# SparkFun_Qwiic_FS3000_1X1.net
KiCad netlist of a schematic drawn in EAGLE
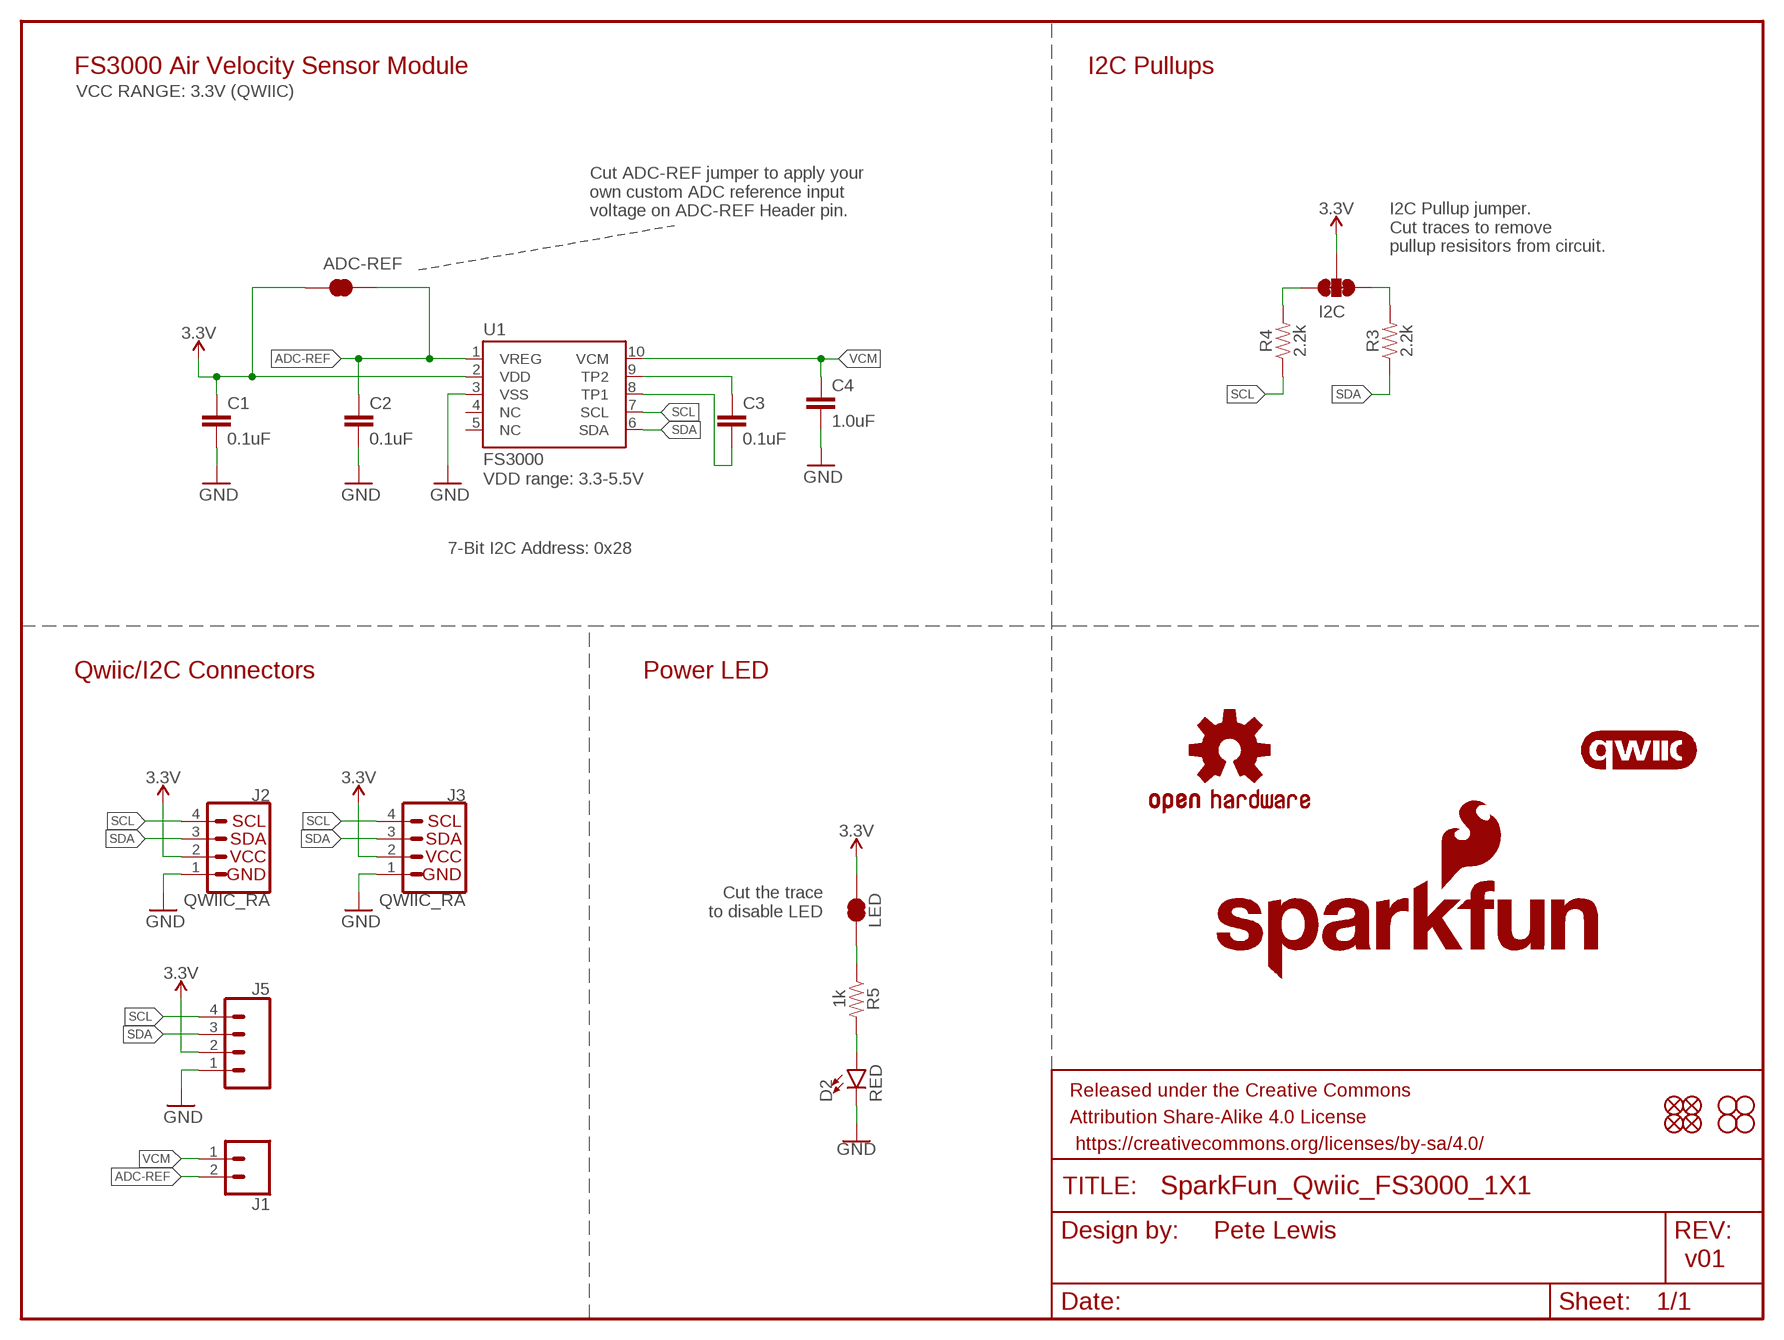
[diagram p0: schematic, sheet 1]

(export (version "E")
  (design (tool "Eeschema 10.0.6"))
  (components
    (comp (ref "ADC-REF")
      (value "JUMPER-SMT_2_NC_TRACE_SILK")
      (footprint "eagle-import:SMT-JUMPER_2_NC_TRACE_SILK")
      (libsource (lib "eagle-import") (part "JUMPER-SMT_2_NC_TRACE_SILK"))
    )
    (comp (ref "C1")
      (value "0.1uF")
      (footprint "eagle-import:0402-TIGHT")
      (libsource (lib "eagle-import") (part "0.1UF-0402T-16V-10%"))
    )
    (comp (ref "C2")
      (value "0.1uF")
      (footprint "eagle-import:0402-TIGHT")
      (libsource (lib "eagle-import") (part "0.1UF-0402T-16V-10%"))
    )
    (comp (ref "C3")
      (value "0.1uF")
      (footprint "eagle-import:0402-TIGHT")
      (libsource (lib "eagle-import") (part "0.1UF-0402T-16V-10%"))
    )
    (comp (ref "C4")
      (value "1.0uF")
      (footprint "eagle-import:0402-TIGHT")
      (libsource (lib "eagle-import") (part "1.0UF-0402T-16V-10%"))
    )
    (comp (ref "D2")
      (value "RED")
      (footprint "eagle-import:LED-0603")
      (libsource (lib "eagle-import") (part "LED-RED0603"))
    )
    (comp (ref "FRAME1")
      (value "FRAME-LETTER")
      (footprint "eagle-import:CREATIVE_COMMONS")
      (libsource (lib "eagle-import") (part "FRAME-LETTER"))
    )
    (comp (ref "I2C")
      (value "JUMPER-SMT_3_2-NC_TRACE_SILK")
      (footprint "eagle-import:SMT-JUMPER_3_2-NC_TRACE_SILK")
      (libsource (lib "eagle-import") (part "JUMPER-SMT_3_2-NC_TRACE_SILK"))
    )
    (comp (ref "J1")
      (value "CONN_021X02_NO_SILK")
      (footprint "eagle-import:1X02_NO_SILK")
      (libsource (lib "eagle-import") (part "CONN_021X02_NO_SILK"))
    )
    (comp (ref "J2")
      (value "QWIIC_RA")
      (footprint "eagle-import:JST04_1MM_RA")
      (libsource (lib "eagle-import") (part "QWIIC_CONNECTORJS-1MM"))
    )
    (comp (ref "J3")
      (value "QWIIC_RA")
      (footprint "eagle-import:JST04_1MM_RA")
      (libsource (lib "eagle-import") (part "QWIIC_CONNECTORJS-1MM"))
    )
    (comp (ref "J5")
      (value "CONN_041X04_NO_SILK")
      (footprint "eagle-import:1X04_NO_SILK")
      (libsource (lib "eagle-import") (part "CONN_041X04_NO_SILK"))
    )
    (comp (ref "JP1")
      (value "LED")
      (footprint "eagle-import:SMT-JUMPER_2_NC_TRACE_SILK")
      (libsource (lib "eagle-import") (part "JUMPER-SMT_2_NC_TRACE_SILK"))
    )
    (comp (ref "JP2")
      (value "FIDUCIALUFIDUCIAL")
      (footprint "eagle-import:FIDUCIAL-MICRO")
      (libsource (lib "eagle-import") (part "FIDUCIALUFIDUCIAL"))
    )
    (comp (ref "JP3")
      (value "STAND-OFF")
      (footprint "eagle-import:STAND-OFF")
      (libsource (lib "eagle-import") (part "STAND-OFF"))
    )
    (comp (ref "JP4")
      (value "STAND-OFF")
      (footprint "eagle-import:STAND-OFF")
      (libsource (lib "eagle-import") (part "STAND-OFF"))
    )
    (comp (ref "JP5")
      (value "FIDUCIALUFIDUCIAL")
      (footprint "eagle-import:FIDUCIAL-MICRO")
      (libsource (lib "eagle-import") (part "FIDUCIALUFIDUCIAL"))
    )
    (comp (ref "JP6")
      (value "FIDUCIALUFIDUCIAL")
      (footprint "eagle-import:FIDUCIAL-MICRO")
      (libsource (lib "eagle-import") (part "FIDUCIALUFIDUCIAL"))
    )
    (comp (ref "JP7")
      (value "STAND-OFF")
      (footprint "eagle-import:STAND-OFF")
      (libsource (lib "eagle-import") (part "STAND-OFF"))
    )
    (comp (ref "JP8")
      (value "STAND-OFF")
      (footprint "eagle-import:STAND-OFF")
      (libsource (lib "eagle-import") (part "STAND-OFF"))
    )
    (comp (ref "JP11")
      (value "FIDUCIALUFIDUCIAL")
      (footprint "eagle-import:FIDUCIAL-MICRO")
      (libsource (lib "eagle-import") (part "FIDUCIALUFIDUCIAL"))
    )
    (comp (ref "LOGO1")
      (value "OSHW-LOGOMINI")
      (footprint "eagle-import:OSHW-LOGO-MINI")
      (libsource (lib "eagle-import") (part "OSHW-LOGOMINI"))
    )
    (comp (ref "LOGO3")
      (value "SFE_LOGO_NAME_FLAME.1_INCH")
      (footprint "eagle-import:SFE_LOGO_NAME_FLAME_.1")
      (libsource (lib "eagle-import") (part "SFE_LOGO_NAME_FLAME.1_INCH"))
    )
    (comp (ref "LOGO4")
      (value "QWIIC_LOGO_5MM")
      (footprint "eagle-import:QWIIC_5MM")
      (libsource (lib "eagle-import") (part "QWIIC_LOGO_5MM"))
    )
    (comp (ref "LOGO5")
      (value "SFE_LOGO_NAME_FLAME.1_INCH")
      (footprint "eagle-import:SFE_LOGO_NAME_FLAME_.1")
      (libsource (lib "eagle-import") (part "SFE_LOGO_NAME_FLAME.1_INCH"))
    )
    (comp (ref "R3")
      (value "2.2k")
      (footprint "eagle-import:0402-TIGHT")
      (libsource (lib "eagle-import") (part "2.2KOHM-0402T-1/16W-1%"))
    )
    (comp (ref "R4")
      (value "2.2k")
      (footprint "eagle-import:0402-TIGHT")
      (libsource (lib "eagle-import") (part "2.2KOHM-0402T-1/16W-1%"))
    )
    (comp (ref "R5")
      (value "1k")
      (footprint "eagle-import:0402-TIGHT")
      (libsource (lib "eagle-import") (part "1KOHM-0402T-1/16W-1%"))
    )
    (comp (ref "U1")
      (value "FS3000")
      (footprint "eagle-import:FS3000")
      (libsource (lib "eagle-import") (part "FS3000"))
    )
  )
  (nets
    (net (code "1") (name "3.3V") (class "Default")
      (node (ref "ADC-REF") (pin "1") (pinfunction "1_1") (pintype "passive"))
      (node (ref "C1") (pin "1") (pinfunction "1_1") (pintype "passive"))
      (node (ref "I2C") (pin "2") (pinfunction "2_2") (pintype "passive"))
      (node (ref "J2") (pin "2") (pinfunction "2_2") (pintype "power_in"))
      (node (ref "J3") (pin "2") (pinfunction "2_2") (pintype "power_in"))
      (node (ref "J5") (pin "2") (pinfunction "2_2") (pintype "passive"))
      (node (ref "JP1") (pin "2") (pinfunction "2_2") (pintype "passive"))
      (node (ref "U1") (pin "2") (pinfunction "VDD_2") (pintype "bidirectional"))
    )
    (net (code "2") (name "ADC-REF") (class "Default")
      (node (ref "ADC-REF") (pin "2") (pinfunction "2_2") (pintype "passive"))
      (node (ref "C2") (pin "1") (pinfunction "1_1") (pintype "passive"))
      (node (ref "J1") (pin "2") (pinfunction "2_2") (pintype "passive"))
      (node (ref "U1") (pin "1") (pinfunction "VREG_1") (pintype "bidirectional"))
    )
    (net (code "3") (name "GND") (class "Default")
      (node (ref "C1") (pin "2") (pinfunction "2_2") (pintype "passive"))
      (node (ref "C2") (pin "2") (pinfunction "2_2") (pintype "passive"))
      (node (ref "C4") (pin "2") (pinfunction "2_2") (pintype "passive"))
      (node (ref "D2") (pin "C") (pinfunction "C_C") (pintype "passive"))
      (node (ref "J2") (pin "1") (pinfunction "1_1") (pintype "power_in"))
      (node (ref "J3") (pin "1") (pinfunction "1_1") (pintype "power_in"))
      (node (ref "J5") (pin "1") (pinfunction "1_1") (pintype "passive"))
      (node (ref "U1") (pin "3") (pinfunction "VSS_3") (pintype "bidirectional"))
    )
    (net (code "4") (name "Net-(D2-PadA)") (class "Default")
      (node (ref "D2") (pin "A") (pinfunction "A_A") (pintype "passive"))
      (node (ref "R5") (pin "2") (pinfunction "2_2") (pintype "passive"))
    )
    (net (code "5") (name "Net-(I2C-Pad1)") (class "Default")
      (node (ref "I2C") (pin "1") (pinfunction "1_1") (pintype "passive"))
      (node (ref "R3") (pin "2") (pinfunction "2_2") (pintype "passive"))
    )
    (net (code "6") (name "Net-(I2C-Pad3)") (class "Default")
      (node (ref "I2C") (pin "3") (pinfunction "3_3") (pintype "passive"))
      (node (ref "R4") (pin "2") (pinfunction "2_2") (pintype "passive"))
    )
    (net (code "7") (name "Net-(JP1-Pad1)") (class "Default")
      (node (ref "JP1") (pin "1") (pinfunction "1_1") (pintype "passive"))
      (node (ref "R5") (pin "1") (pinfunction "1_1") (pintype "passive"))
    )
    (net (code "8") (name "Net-(U1-TP1)") (class "Default")
      (node (ref "C3") (pin "2") (pinfunction "2_2") (pintype "passive"))
      (node (ref "U1") (pin "8") (pinfunction "TP1_8") (pintype "bidirectional"))
    )
    (net (code "9") (name "Net-(U1-TP2)") (class "Default")
      (node (ref "C3") (pin "1") (pinfunction "1_1") (pintype "passive"))
      (node (ref "U1") (pin "9") (pinfunction "TP2_9") (pintype "bidirectional"))
    )
    (net (code "10") (name "SCL") (class "Default")
      (node (ref "J2") (pin "4") (pinfunction "4_4") (pintype "passive"))
      (node (ref "J3") (pin "4") (pinfunction "4_4") (pintype "passive"))
      (node (ref "J5") (pin "4") (pinfunction "4_4") (pintype "passive"))
      (node (ref "R4") (pin "1") (pinfunction "1_1") (pintype "passive"))
      (node (ref "U1") (pin "7") (pinfunction "SCL_7") (pintype "bidirectional"))
    )
    (net (code "11") (name "SDA") (class "Default")
      (node (ref "J2") (pin "3") (pinfunction "3_3") (pintype "passive"))
      (node (ref "J3") (pin "3") (pinfunction "3_3") (pintype "passive"))
      (node (ref "J5") (pin "3") (pinfunction "3_3") (pintype "passive"))
      (node (ref "R3") (pin "1") (pinfunction "1_1") (pintype "passive"))
      (node (ref "U1") (pin "6") (pinfunction "SDA_6") (pintype "bidirectional"))
    )
    (net (code "12") (name "VCM") (class "Default")
      (node (ref "C4") (pin "1") (pinfunction "1_1") (pintype "passive"))
      (node (ref "J1") (pin "1") (pinfunction "1_1") (pintype "passive"))
      (node (ref "U1") (pin "10") (pinfunction "VCM_10") (pintype "bidirectional"))
    )
    (net (code "13") (name "unconnected-(U1-NC-Pad4)") (class "Default")
      (node (ref "U1") (pin "4") (pinfunction "NC_4") (pintype "no_connect"))
    )
    (net (code "14") (name "unconnected-(U1-NC-Pad5)") (class "Default")
      (node (ref "U1") (pin "5") (pinfunction "NC_5") (pintype "no_connect"))
    )
  )
)
